# DWM_Breakout.net
KiCad netlist of a schematic drawn in EAGLE
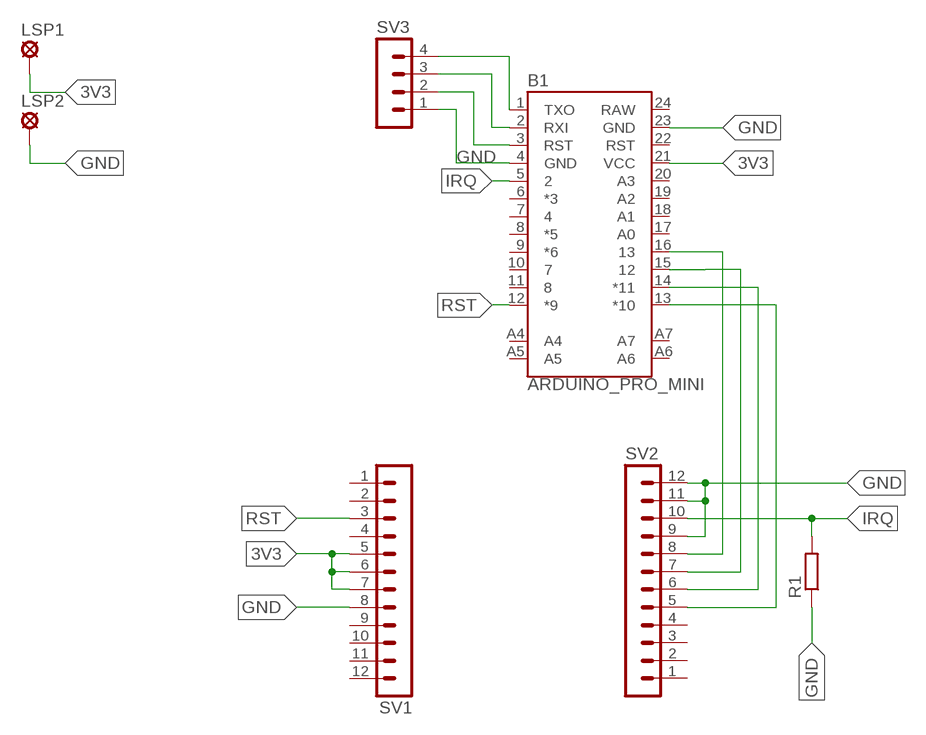
[diagram p0: schematic, sheet 1]

(export (version "E")
  (design (tool "Eeschema 10.0.6"))
  (components
    (comp (ref "B1")
      (value "ARDUINO_PRO_MINI")
      (footprint "eagle-import:ARDUINO_PRO_MINI")
      (libsource (lib "eagle-import") (part "ARDUINO_PRO_MINI"))
    )
    (comp (ref "LSP1")
      (value "SE14")
      (footprint "eagle-import:SE14")
      (libsource (lib "eagle-import") (part "SE14"))
    )
    (comp (ref "LSP2")
      (value "SE14")
      (footprint "eagle-import:SE14")
      (libsource (lib "eagle-import") (part "SE14"))
    )
    (comp (ref "R1")
      (value "R-EU_0207/10")
      (footprint "eagle-import:0207_10")
      (libsource (lib "eagle-import") (part "R-EU_0207/10"))
    )
    (comp (ref "SV1")
      (value "MA12-1")
      (footprint "eagle-import:MA12-1")
      (libsource (lib "eagle-import") (part "MA12-1"))
    )
    (comp (ref "SV2")
      (value "MA12-1")
      (footprint "eagle-import:MA12-1")
      (libsource (lib "eagle-import") (part "MA12-1"))
    )
    (comp (ref "SV3")
      (value "MA04-1")
      (footprint "eagle-import:MA04-1")
      (libsource (lib "eagle-import") (part "MA04-1"))
    )
  )
  (nets
    (net (code "1") (name "/RAW") (class "Default")
      (node (ref "B1") (pin "24") (pinfunction "RAW_24") (pintype "power_in"))
    )
    (net (code "2") (name "3V3") (class "Default")
      (node (ref "B1") (pin "21") (pinfunction "VCC_21") (pintype "power_in"))
      (node (ref "LSP1") (pin "MP") (pinfunction "MP_MP") (pintype "passive"))
      (node (ref "SV1") (pin "5") (pinfunction "5_5") (pintype "passive"))
      (node (ref "SV1") (pin "6") (pinfunction "6_6") (pintype "passive"))
      (node (ref "SV1") (pin "7") (pinfunction "7_7") (pintype "passive"))
    )
    (net (code "3") (name "GND") (class "Default")
      (node (ref "B1") (pin "23") (pinfunction "GND_23") (pintype "power_in"))
      (node (ref "B1") (pin "4") (pinfunction "GND_4") (pintype "power_in"))
      (node (ref "LSP2") (pin "MP") (pinfunction "MP_MP") (pintype "passive"))
      (node (ref "R1") (pin "1") (pinfunction "1_1") (pintype "passive"))
      (node (ref "SV1") (pin "8") (pinfunction "8_8") (pintype "passive"))
      (node (ref "SV2") (pin "11") (pinfunction "11_11") (pintype "passive"))
      (node (ref "SV2") (pin "12") (pinfunction "12_12") (pintype "passive"))
      (node (ref "SV2") (pin "9") (pinfunction "9_9") (pintype "passive"))
      (node (ref "SV3") (pin "1") (pinfunction "1_1") (pintype "passive"))
    )
    (net (code "4") (name "IRQ") (class "Default")
      (node (ref "B1") (pin "5") (pinfunction "2_5") (pintype "bidirectional"))
      (node (ref "R1") (pin "2") (pinfunction "2_2") (pintype "passive"))
      (node (ref "SV2") (pin "10") (pinfunction "10_10") (pintype "passive"))
    )
    (net (code "5") (name "Net-(B1-*10)") (class "Default")
      (node (ref "B1") (pin "13") (pinfunction "*10_13") (pintype "bidirectional"))
      (node (ref "SV2") (pin "5") (pinfunction "5_5") (pintype "passive"))
    )
    (net (code "6") (name "Net-(B1-*11)") (class "Default")
      (node (ref "B1") (pin "14") (pinfunction "*11_14") (pintype "bidirectional"))
      (node (ref "SV2") (pin "6") (pinfunction "6_6") (pintype "passive"))
    )
    (net (code "7") (name "Net-(B1-12)") (class "Default")
      (node (ref "B1") (pin "15") (pinfunction "12_15") (pintype "bidirectional"))
      (node (ref "SV2") (pin "7") (pinfunction "7_7") (pintype "passive"))
    )
    (net (code "8") (name "Net-(B1-13)") (class "Default")
      (node (ref "B1") (pin "16") (pinfunction "13_16") (pintype "bidirectional"))
      (node (ref "SV2") (pin "8") (pinfunction "8_8") (pintype "passive"))
    )
    (net (code "9") (name "Net-(B1-RST-Pad3)") (class "Default")
      (node (ref "B1") (pin "3") (pinfunction "RST_3") (pintype "bidirectional"))
      (node (ref "SV3") (pin "2") (pinfunction "2_2") (pintype "passive"))
    )
    (net (code "10") (name "Net-(B1-RXI)") (class "Default")
      (node (ref "B1") (pin "2") (pinfunction "RXI_2") (pintype "bidirectional"))
      (node (ref "SV3") (pin "3") (pinfunction "3_3") (pintype "passive"))
    )
    (net (code "11") (name "Net-(B1-TXO)") (class "Default")
      (node (ref "B1") (pin "1") (pinfunction "TXO_1") (pintype "bidirectional"))
      (node (ref "SV3") (pin "4") (pinfunction "4_4") (pintype "passive"))
    )
    (net (code "12") (name "RST") (class "Default")
      (node (ref "B1") (pin "12") (pinfunction "*9_12") (pintype "bidirectional"))
      (node (ref "SV1") (pin "3") (pinfunction "3_3") (pintype "passive"))
    )
    (net (code "13") (name "unconnected-(B1-*3-Pad6)") (class "Default")
      (node (ref "B1") (pin "6") (pinfunction "*3_6") (pintype "bidirectional"))
    )
    (net (code "14") (name "unconnected-(B1-*5-Pad8)") (class "Default")
      (node (ref "B1") (pin "8") (pinfunction "*5_8") (pintype "bidirectional"))
    )
    (net (code "15") (name "unconnected-(B1-*6-Pad9)") (class "Default")
      (node (ref "B1") (pin "9") (pinfunction "*6_9") (pintype "bidirectional"))
    )
    (net (code "16") (name "unconnected-(B1-4-Pad7)") (class "Default")
      (node (ref "B1") (pin "7") (pinfunction "4_7") (pintype "bidirectional"))
    )
    (net (code "17") (name "unconnected-(B1-7-Pad10)") (class "Default")
      (node (ref "B1") (pin "10") (pinfunction "7_10") (pintype "bidirectional"))
    )
    (net (code "18") (name "unconnected-(B1-8-Pad11)") (class "Default")
      (node (ref "B1") (pin "11") (pinfunction "8_11") (pintype "bidirectional"))
    )
    (net (code "19") (name "unconnected-(B1-A0-Pad17)") (class "Default")
      (node (ref "B1") (pin "17") (pinfunction "A0_17") (pintype "bidirectional"))
    )
    (net (code "20") (name "unconnected-(B1-A1-Pad18)") (class "Default")
      (node (ref "B1") (pin "18") (pinfunction "A1_18") (pintype "bidirectional"))
    )
    (net (code "21") (name "unconnected-(B1-A2-Pad19)") (class "Default")
      (node (ref "B1") (pin "19") (pinfunction "A2_19") (pintype "bidirectional"))
    )
    (net (code "22") (name "unconnected-(B1-A3-Pad20)") (class "Default")
      (node (ref "B1") (pin "20") (pinfunction "A3_20") (pintype "bidirectional"))
    )
    (net (code "23") (name "unconnected-(B1-PadA4)") (class "Default")
      (node (ref "B1") (pin "A4") (pinfunction "A4_A4") (pintype "bidirectional"))
    )
    (net (code "24") (name "unconnected-(B1-PadA5)") (class "Default")
      (node (ref "B1") (pin "A5") (pinfunction "A5_A5") (pintype "bidirectional"))
    )
    (net (code "25") (name "unconnected-(B1-PadA6)") (class "Default")
      (node (ref "B1") (pin "A6") (pinfunction "A6_A6") (pintype "bidirectional"))
    )
    (net (code "26") (name "unconnected-(B1-PadA7)") (class "Default")
      (node (ref "B1") (pin "A7") (pinfunction "A7_A7") (pintype "bidirectional"))
    )
    (net (code "27") (name "unconnected-(B1-RST-Pad22)") (class "Default")
      (node (ref "B1") (pin "22") (pinfunction "RST_22") (pintype "bidirectional"))
    )
    (net (code "28") (name "unconnected-(SV1-Pad1)") (class "Default")
      (node (ref "SV1") (pin "1") (pinfunction "1_1") (pintype "passive"))
    )
    (net (code "29") (name "unconnected-(SV1-Pad2)") (class "Default")
      (node (ref "SV1") (pin "2") (pinfunction "2_2") (pintype "passive"))
    )
    (net (code "30") (name "unconnected-(SV1-Pad4)") (class "Default")
      (node (ref "SV1") (pin "4") (pinfunction "4_4") (pintype "passive"))
    )
    (net (code "31") (name "unconnected-(SV1-Pad9)") (class "Default")
      (node (ref "SV1") (pin "9") (pinfunction "9_9") (pintype "passive"))
    )
    (net (code "32") (name "unconnected-(SV1-Pad10)") (class "Default")
      (node (ref "SV1") (pin "10") (pinfunction "10_10") (pintype "passive"))
    )
    (net (code "33") (name "unconnected-(SV1-Pad11)") (class "Default")
      (node (ref "SV1") (pin "11") (pinfunction "11_11") (pintype "passive"))
    )
    (net (code "34") (name "unconnected-(SV1-Pad12)") (class "Default")
      (node (ref "SV1") (pin "12") (pinfunction "12_12") (pintype "passive"))
    )
    (net (code "35") (name "unconnected-(SV2-Pad1)") (class "Default")
      (node (ref "SV2") (pin "1") (pinfunction "1_1") (pintype "passive"))
    )
    (net (code "36") (name "unconnected-(SV2-Pad2)") (class "Default")
      (node (ref "SV2") (pin "2") (pinfunction "2_2") (pintype "passive"))
    )
    (net (code "37") (name "unconnected-(SV2-Pad3)") (class "Default")
      (node (ref "SV2") (pin "3") (pinfunction "3_3") (pintype "passive"))
    )
    (net (code "38") (name "unconnected-(SV2-Pad4)") (class "Default")
      (node (ref "SV2") (pin "4") (pinfunction "4_4") (pintype "passive"))
    )
  )
)
